# SCH_Uno-CellTap.net
KiCad netlist of a schematic drawn in Altium Designer
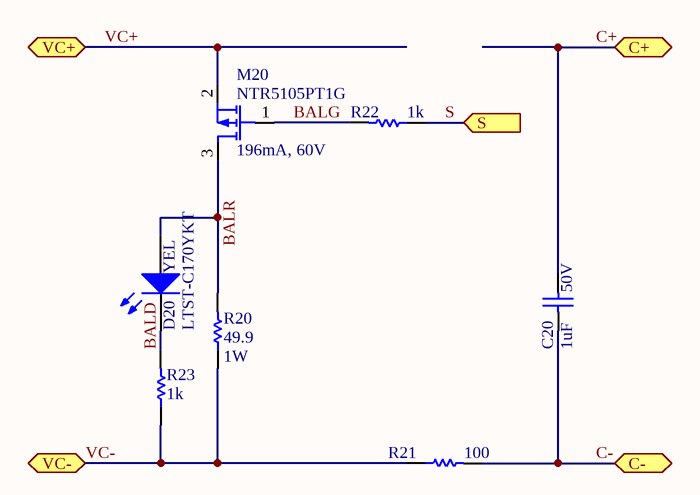
[diagram p0: SCH Uno-CellTap.SchDoc]

(export (version "E")
  (design (tool "Eeschema 10.0.6"))
  (components
    (comp (ref "C20")
      (value "1uF")
      (footprint "CAPC2012N")
      (description "Capacitor")
      (fields (field (name "RATED") "50V") (field (name "Comment") "CL21F105ZBFNNNE"))
      (libsource (lib "Miscellaneous Devices") (part "Cap"))
    )
    (comp (ref "D20")
      (value "LTST-C170YKT")
      (footprint "DIO2012N-Y")
      (description "SMT Yellow Si LED")
      (fields (field (name "ALTIUM_VALUE") "YEL"))
      (libsource (lib "LIB SCH ArduinoBMS") (part "LTST-C170YKT"))
    )
    (comp (ref "M20")
      (value "NTR5105PT1G")
      (footprint "SOT23-3N")
      (description "P-Channel MOSFET")
      (fields (field (name "RATED") "196mA, 60V"))
      (libsource (lib "Miscellaneous Devices") (part "MOSFET-P"))
    )
    (comp (ref "R20")
      (value "49.9")
      (footprint "RESC6432N")
      (description "Resistor, 1W")
      (fields (field (name "RATED") "1W") (field (name "Comment") "RMCF2512FT49R9"))
      (libsource (lib "Miscellaneous Devices") (part "Res1"))
    )
    (comp (ref "R21")
      (value "100")
      (footprint "RESC2012N")
      (description "Resistor")
      (fields (field (name "Comment") "ERJ-6ENF1000V"))
      (libsource (lib "Miscellaneous Devices") (part "Res1"))
    )
    (comp (ref "R22")
      (value "1k")
      (footprint "RESC2012N")
      (description "Resistor")
      (fields (field (name "Comment") "ERJ-6ENF1001V"))
      (libsource (lib "Miscellaneous Devices") (part "Res1"))
    )
    (comp (ref "R23")
      (value "1k")
      (footprint "RESC2012N")
      (description "Resistor")
      (fields (field (name "Comment") "ERJ-6ENF1001V"))
      (libsource (lib "Miscellaneous Devices") (part "Res1"))
    )
  )
  (nets
    (net (code "1") (name "/BALD") (class "Default")
      (node (ref "D20") (pin "2") (pinfunction "K_2") (pintype "passive"))
      (node (ref "R23") (pin "2") (pinfunction "2_2") (pintype "passive"))
    )
    (net (code "2") (name "/BALG") (class "Default")
      (node (ref "M20") (pin "1") (pinfunction "G_1") (pintype "passive"))
      (node (ref "R22") (pin "2") (pinfunction "2_2") (pintype "passive"))
    )
    (net (code "3") (name "/BALR") (class "Default")
      (node (ref "D20") (pin "1") (pinfunction "A_1") (pintype "passive"))
      (node (ref "M20") (pin "3") (pinfunction "D_3") (pintype "passive"))
      (node (ref "R20") (pin "2") (pinfunction "2_2") (pintype "passive"))
    )
    (net (code "4") (name "/C+") (class "Default")
      (node (ref "C20") (pin "1") (pinfunction "1_1") (pintype "passive"))
    )
    (net (code "5") (name "/C-") (class "Default")
      (node (ref "C20") (pin "2") (pinfunction "2_2") (pintype "passive"))
      (node (ref "R21") (pin "2") (pinfunction "2_2") (pintype "passive"))
    )
    (net (code "6") (name "/S") (class "Default")
      (node (ref "R22") (pin "1") (pinfunction "1_1") (pintype "passive"))
    )
    (net (code "7") (name "/VC+") (class "Default")
      (node (ref "M20") (pin "2") (pinfunction "S_2") (pintype "passive"))
    )
    (net (code "8") (name "/VC-") (class "Default")
      (node (ref "R20") (pin "1") (pinfunction "1_1") (pintype "passive"))
      (node (ref "R21") (pin "1") (pinfunction "1_1") (pintype "passive"))
      (node (ref "R23") (pin "1") (pinfunction "1_1") (pintype "passive"))
    )
  )
)
